# vio-buffer.net
KiCad netlist of a schematic drawn in Altium Designer
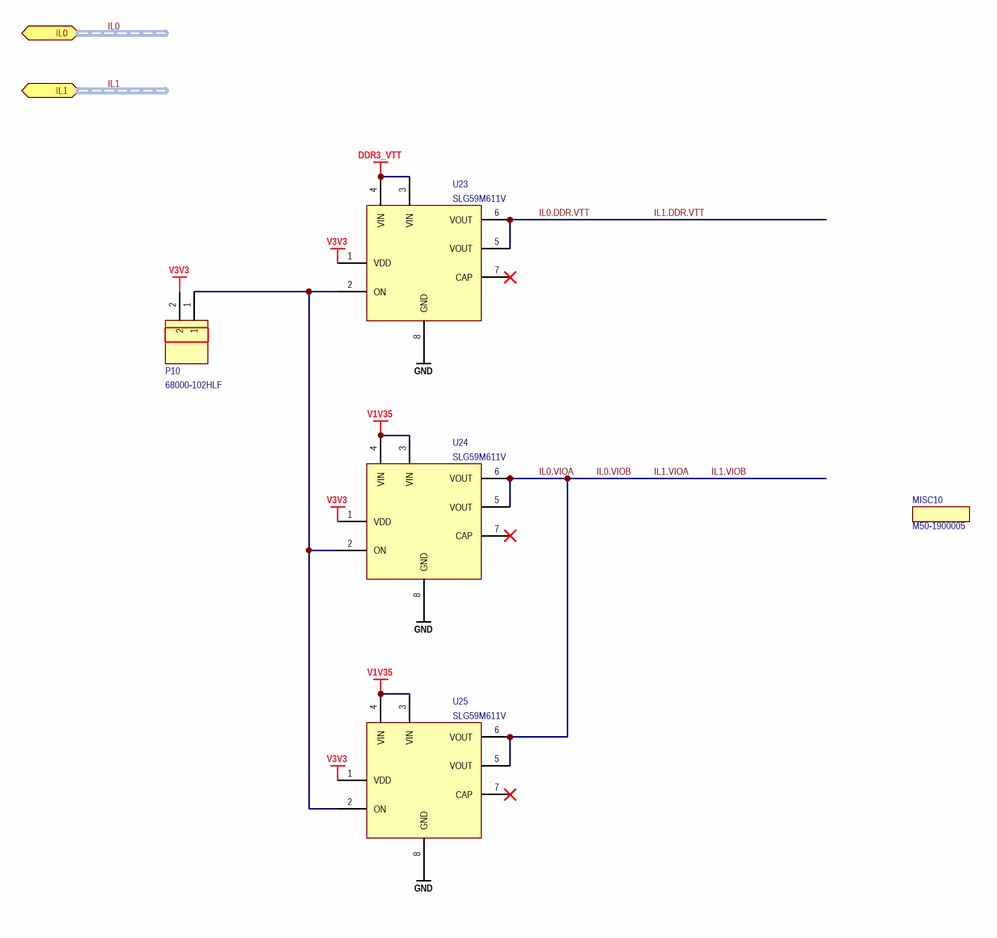
[diagram p0: vio-buffer.SchDoc]

(export (version "E")
  (design (tool "Eeschema 10.0.6"))
  (components
    (comp (ref "MISC10")
      (value "M50-1900005")
      (description "1.27mm Jumper Socket")
      (fields (field (name "MANUFACTURER") "Harwin"))
      (libsource (lib "harwin") (part "M50-1900005"))
    )
    (comp (ref "P10")
      (value "68000-102HLF")
      (footprint "68000-102HLF")
      (description "Connector; Header; 2 Position; 0.1\" Pitch")
      (fields (field (name "MANUFACTURER") "FCI"))
      (libsource (lib "fci") (part "68000-102HLF"))
    )
    (comp (ref "U23")
      (value "SLG59M611V")
      (footprint "silego:SLG59M611V")
      (description "Ultra-small 4.0A Load Switch with Reverse Current Blocking")
      (fields (field (name "MANUFACTURER") "Silego"))
      (libsource (lib "silego") (part "SLG59M611V"))
    )
    (comp (ref "U24")
      (value "SLG59M611V")
      (footprint "silego:SLG59M611V")
      (description "Ultra-small 4.0A Load Switch with Reverse Current Blocking")
      (fields (field (name "MANUFACTURER") "Silego"))
      (libsource (lib "silego") (part "SLG59M611V"))
    )
    (comp (ref "U25")
      (value "SLG59M611V")
      (footprint "silego:SLG59M611V")
      (description "Ultra-small 4.0A Load Switch with Reverse Current Blocking")
      (fields (field (name "MANUFACTURER") "Silego"))
      (libsource (lib "silego") (part "SLG59M611V"))
    )
  )
  (nets
    (net (code "3") (name "/IL0.DDR.VTT") (class "Default")
      (node (ref "U23") (pin "5") (pinfunction "VOUT_5") (pintype "passive"))
      (node (ref "U23") (pin "6") (pinfunction "VOUT_6") (pintype "passive"))
    )
    (net (code "4") (name "/IL0.VIOA") (class "Default")
      (node (ref "U24") (pin "5") (pinfunction "VOUT_5") (pintype "passive"))
      (node (ref "U24") (pin "6") (pinfunction "VOUT_6") (pintype "passive"))
      (node (ref "U25") (pin "5") (pinfunction "VOUT_5") (pintype "passive"))
      (node (ref "U25") (pin "6") (pinfunction "VOUT_6") (pintype "passive"))
    )
    (net (code "7") (name "DDR3_VTT") (class "Default")
      (node (ref "U23") (pin "3") (pinfunction "VIN_3") (pintype "passive"))
      (node (ref "U23") (pin "4") (pinfunction "VIN_4") (pintype "passive"))
    )
    (net (code "8") (name "GND") (class "Default")
      (node (ref "U23") (pin "8") (pinfunction "GND_8") (pintype "passive"))
      (node (ref "U24") (pin "8") (pinfunction "GND_8") (pintype "passive"))
      (node (ref "U25") (pin "8") (pinfunction "GND_8") (pintype "passive"))
    )
    (net (code "9") (name "Net-(U23-ON)") (class "Default")
      (node (ref "P10") (pin "1") (pinfunction "1_1") (pintype "passive"))
      (node (ref "U23") (pin "2") (pinfunction "ON_2") (pintype "passive"))
      (node (ref "U24") (pin "2") (pinfunction "ON_2") (pintype "passive"))
      (node (ref "U25") (pin "2") (pinfunction "ON_2") (pintype "passive"))
    )
    (net (code "10") (name "V1V35") (class "Default")
      (node (ref "U24") (pin "3") (pinfunction "VIN_3") (pintype "passive"))
      (node (ref "U24") (pin "4") (pinfunction "VIN_4") (pintype "passive"))
      (node (ref "U25") (pin "3") (pinfunction "VIN_3") (pintype "passive"))
      (node (ref "U25") (pin "4") (pinfunction "VIN_4") (pintype "passive"))
    )
    (net (code "11") (name "V3V3") (class "Default")
      (node (ref "P10") (pin "2") (pinfunction "2_2") (pintype "passive"))
      (node (ref "U23") (pin "1") (pinfunction "VDD_1") (pintype "passive"))
      (node (ref "U24") (pin "1") (pinfunction "VDD_1") (pintype "passive"))
      (node (ref "U25") (pin "1") (pinfunction "VDD_1") (pintype "passive"))
    )
    (net (code "12") (name "unconnected-(U23-CAP-Pad7)") (class "Default")
      (node (ref "U23") (pin "7") (pinfunction "CAP_7") (pintype "passive+no_connect"))
    )
    (net (code "13") (name "unconnected-(U24-CAP-Pad7)") (class "Default")
      (node (ref "U24") (pin "7") (pinfunction "CAP_7") (pintype "passive+no_connect"))
    )
    (net (code "14") (name "unconnected-(U25-CAP-Pad7)") (class "Default")
      (node (ref "U25") (pin "7") (pinfunction "CAP_7") (pintype "passive+no_connect"))
    )
  )
)
